# PROIECT_TSC_schematic.net
KiCad netlist of a schematic drawn in EAGLE
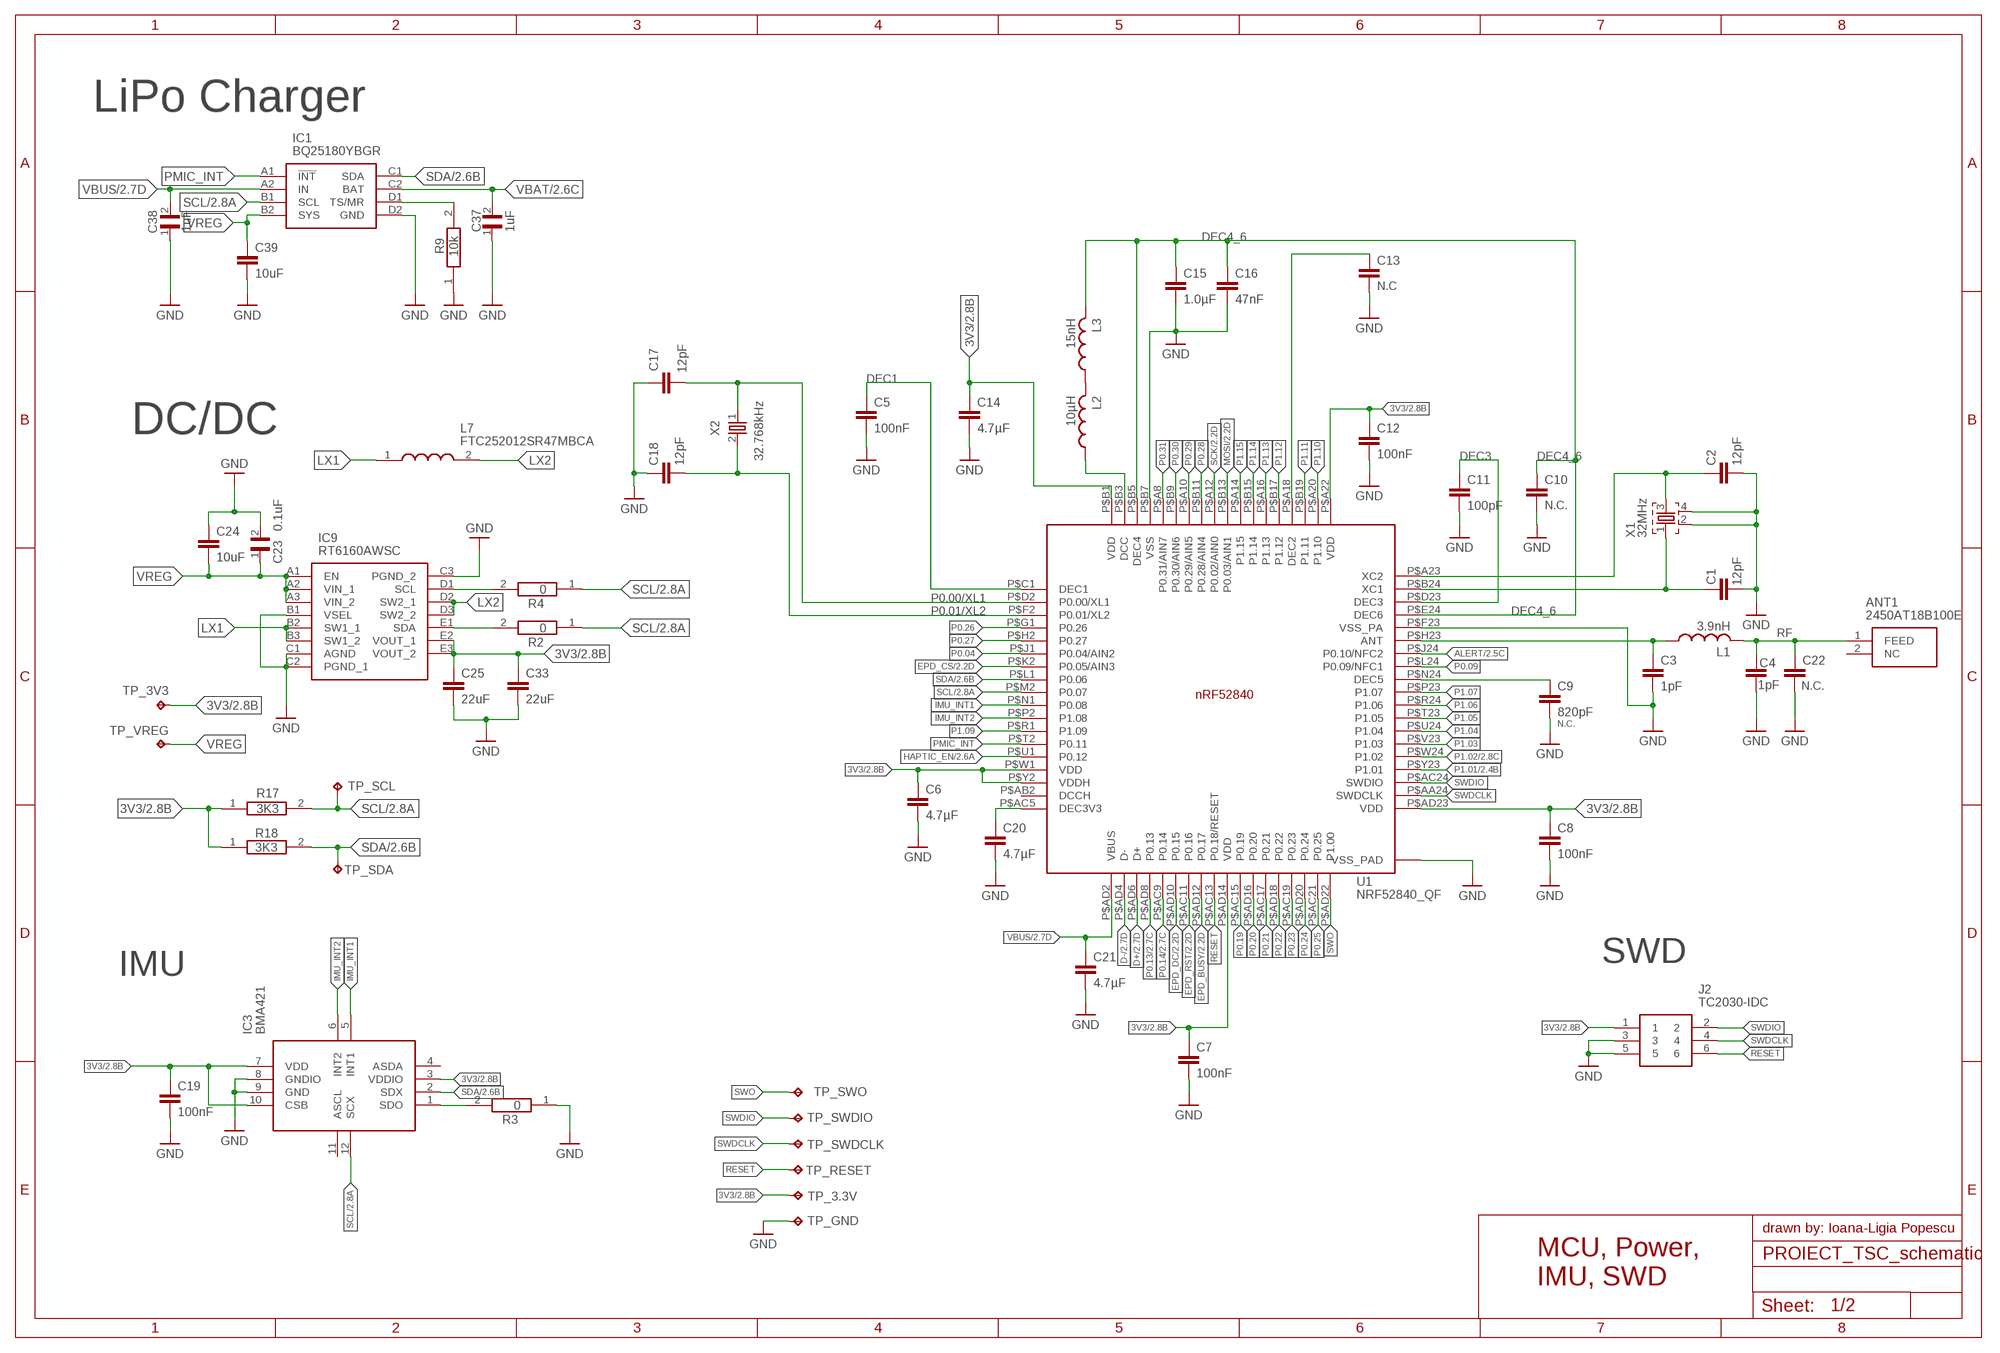
[diagram p0: schematic, sheet 1]
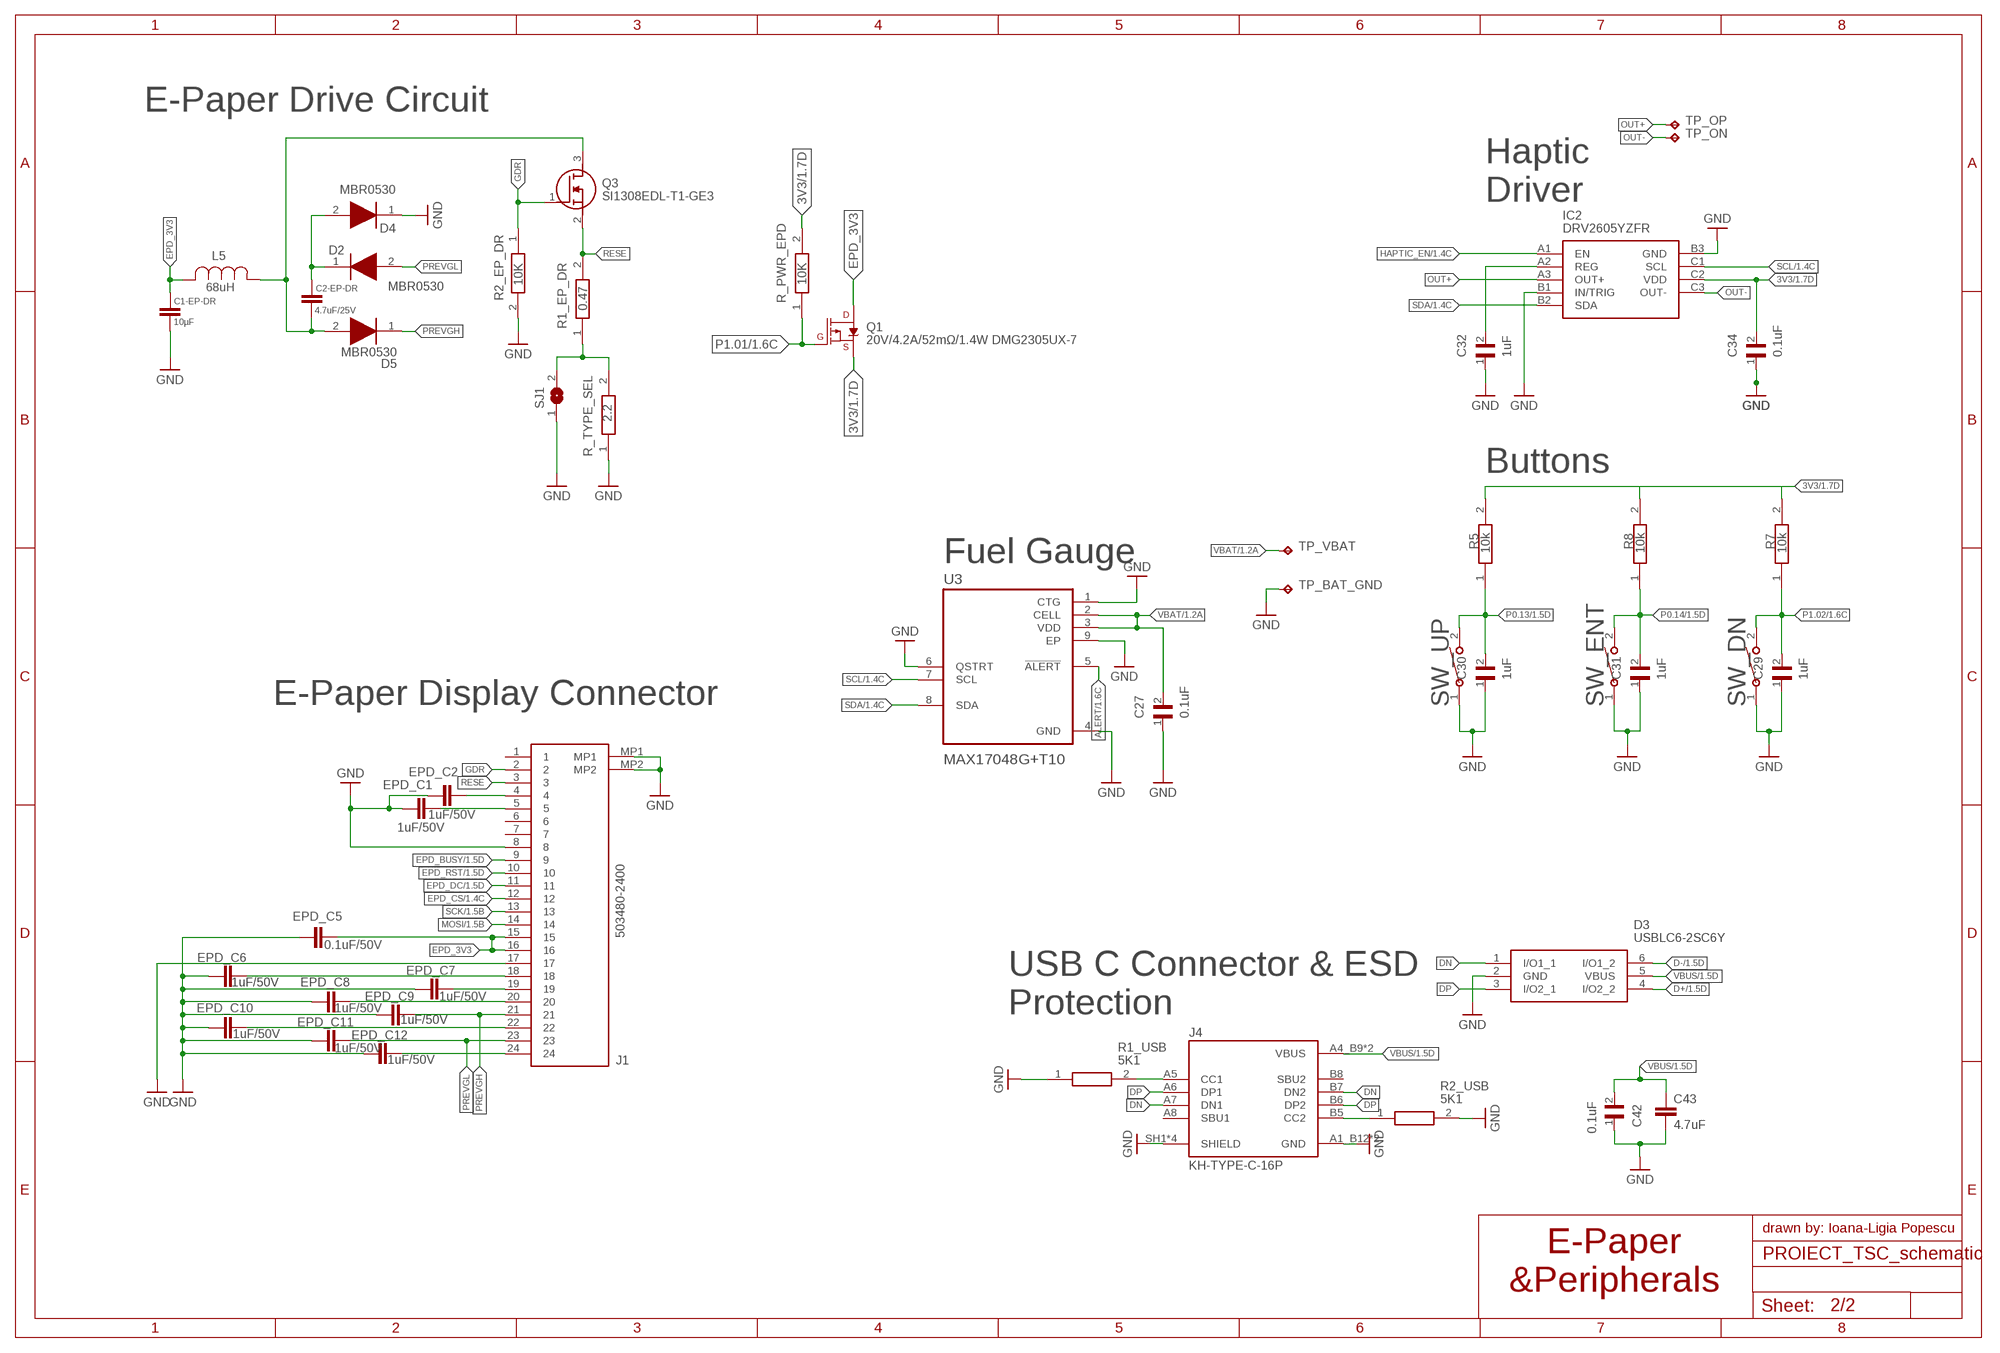
[diagram p1: schematic, sheet 2]

(export (version "E")
  (design (tool "Eeschema 10.0.6"))
  (components
    (comp (ref "ANT1")
      (value "2450AT18B100E")
      (footprint "eagle-import:2450AT18B100E_ANTC3216X140N")
      (fields (field (name "MOUSER_PART_NUMBER") "609-2450AT18B100E"))
      (libsource (lib "eagle-import") (part "2450AT18B100E_2450AT18B100E"))
    )
    (comp (ref "C1")
      (value "12pF")
      (footprint "eagle-import:NORDIC_NRF_3_RESC0201_L")
      (libsource (lib "eagle-import") (part "NORDIC_NRF_3_CAPACITOR_0201_L"))
    )
    (comp (ref "C2")
      (value "12pF")
      (footprint "eagle-import:NORDIC_NRF_3_RESC0201_L")
      (libsource (lib "eagle-import") (part "NORDIC_NRF_3_CAPACITOR_0201_L"))
    )
    (comp (ref "C3")
      (value "1pF")
      (footprint "eagle-import:NORDIC_NRF_3_RESC0201_L")
      (libsource (lib "eagle-import") (part "NORDIC_NRF_3_CAPACITOR_0201_L"))
    )
    (comp (ref "C4")
      (value "1pF")
      (footprint "eagle-import:NORDIC_NRF_3_RESC0201_L")
      (libsource (lib "eagle-import") (part "NORDIC_NRF_3_CAPACITOR_0201_L"))
    )
    (comp (ref "C5")
      (value "100nF")
      (footprint "eagle-import:NORDIC_NRF_3_RESC0201_L")
      (libsource (lib "eagle-import") (part "NORDIC_NRF_3_CAPACITOR_0201_L"))
    )
    (comp (ref "C6")
      (value "4.7µF")
      (footprint "eagle-import:ESP32_C6_LIBRARY_1_ESP32_WROVER_EAGLE-LTSPICE_C0402")
      (libsource (lib "eagle-import") (part "ESP32_C6_LIBRARY_1_ESP32_WROVER_EAGLE-LTSPICE_CC0402"))
    )
    (comp (ref "C7")
      (value "100nF")
      (footprint "eagle-import:NORDIC_NRF_3_RESC0201_L")
      (libsource (lib "eagle-import") (part "NORDIC_NRF_3_CAPACITOR_0201_L"))
    )
    (comp (ref "C8")
      (value "100nF")
      (footprint "eagle-import:NORDIC_NRF_3_RESC0201_L")
      (libsource (lib "eagle-import") (part "NORDIC_NRF_3_CAPACITOR_0201_L"))
    )
    (comp (ref "C9")
      (value "820pF")
      (footprint "eagle-import:NORDIC_NRF_3_RESC0201_L")
      (libsource (lib "eagle-import") (part "NORDIC_NRF_3_CAPACITOR_0201_L"))
    )
    (comp (ref "C10")
      (value "NORDIC_NRF_3_CAPACITOR_0201_L")
      (footprint "eagle-import:NORDIC_NRF_3_RESC0201_L")
      (libsource (lib "eagle-import") (part "NORDIC_NRF_3_CAPACITOR_0201_L"))
    )
    (comp (ref "C11")
      (value "100pF")
      (footprint "eagle-import:NORDIC_NRF_3_RESC0201_L")
      (libsource (lib "eagle-import") (part "NORDIC_NRF_3_CAPACITOR_0201_L"))
    )
    (comp (ref "C12")
      (value "100nF")
      (footprint "eagle-import:NORDIC_NRF_3_RESC0201_L")
      (libsource (lib "eagle-import") (part "NORDIC_NRF_3_CAPACITOR_0201_L"))
    )
    (comp (ref "C13")
      (value "NORDIC_NRF_3_CAPACITOR_0201_L")
      (footprint "eagle-import:NORDIC_NRF_3_RESC0201_L")
      (libsource (lib "eagle-import") (part "NORDIC_NRF_3_CAPACITOR_0201_L"))
    )
    (comp (ref "C14")
      (value "4.7µF")
      (footprint "eagle-import:ESP32_C6_LIBRARY_1_ESP32_WROVER_EAGLE-LTSPICE_C0402")
      (libsource (lib "eagle-import") (part "ESP32_C6_LIBRARY_1_ESP32_WROVER_EAGLE-LTSPICE_CC0402"))
    )
    (comp (ref "C15")
      (value "1.0µF")
      (footprint "eagle-import:ESP32_C6_LIBRARY_1_ESP32_WROVER_EAGLE-LTSPICE_C0402")
      (libsource (lib "eagle-import") (part "ESP32_C6_LIBRARY_1_ESP32_WROVER_EAGLE-LTSPICE_CC0402"))
    )
    (comp (ref "C16")
      (value "47nF")
      (footprint "eagle-import:NORDIC_NRF_3_RESC0201_L")
      (libsource (lib "eagle-import") (part "NORDIC_NRF_3_CAPACITOR_0201_L"))
    )
    (comp (ref "C17")
      (value "12pF")
      (footprint "eagle-import:NORDIC_NRF_3_RESC0201_L")
      (libsource (lib "eagle-import") (part "NORDIC_NRF_3_CAPACITOR_0201_L"))
    )
    (comp (ref "C18")
      (value "12pF")
      (footprint "eagle-import:NORDIC_NRF_3_RESC0201_L")
      (libsource (lib "eagle-import") (part "NORDIC_NRF_3_CAPACITOR_0201_L"))
    )
    (comp (ref "C19")
      (value "100nF")
      (footprint "eagle-import:NORDIC_NRF_3_RESC0201_L")
      (libsource (lib "eagle-import") (part "NORDIC_NRF_3_CAPACITOR_0201_L"))
    )
    (comp (ref "C20")
      (value "4.7µF")
      (footprint "eagle-import:ESP32_C6_LIBRARY_1_ESP32_WROVER_EAGLE-LTSPICE_C0402")
      (libsource (lib "eagle-import") (part "ESP32_C6_LIBRARY_1_ESP32_WROVER_EAGLE-LTSPICE_CC0402"))
    )
    (comp (ref "C21")
      (value "4.7µF")
      (footprint "eagle-import:ESP32_C6_LIBRARY_1_ESP32_WROVER_EAGLE-LTSPICE_C0402")
      (libsource (lib "eagle-import") (part "ESP32_C6_LIBRARY_1_ESP32_WROVER_EAGLE-LTSPICE_CC0402"))
    )
    (comp (ref "C22")
      (value "NORDIC_NRF_3_CAPACITOR_0201_L")
      (footprint "eagle-import:NORDIC_NRF_3_RESC0201_L")
      (libsource (lib "eagle-import") (part "NORDIC_NRF_3_CAPACITOR_0201_L"))
    )
    (comp (ref "C23")
      (value "0.1uF")
      (footprint "eagle-import:GRM011R60J152KE01L_2_CAPC0201X13N")
      (fields (field (name "MF") "Murata") (field (name "MP") "GRM011R60J152KE01L"))
      (libsource (lib "eagle-import") (part "GRM011R60J152KE01L_2_GRM011R60J152KE01L"))
    )
    (comp (ref "C24")
      (value "10uF")
      (footprint "eagle-import:ESP32_C6_LIBRARY_1_ESP32_WROVER_EAGLE-LTSPICE_C0402")
      (libsource (lib "eagle-import") (part "ESP32_C6_LIBRARY_1_ESP32_WROVER_EAGLE-LTSPICE_CC0402"))
    )
    (comp (ref "C25")
      (value "22uF")
      (footprint "eagle-import:ESP32_C6_LIBRARY_1_ESP32_WROVER_EAGLE-LTSPICE_C0402")
      (libsource (lib "eagle-import") (part "ESP32_C6_LIBRARY_1_ESP32_WROVER_EAGLE-LTSPICE_CC0402"))
    )
    (comp (ref "C33")
      (value "22uF")
      (footprint "eagle-import:ESP32_C6_LIBRARY_1_ESP32_WROVER_EAGLE-LTSPICE_C0402")
      (libsource (lib "eagle-import") (part "ESP32_C6_LIBRARY_1_ESP32_WROVER_EAGLE-LTSPICE_CC0402"))
    )
    (comp (ref "C37")
      (value "1uF")
      (footprint "eagle-import:GRM011R60J152KE01L_2_CAPC0201X13N")
      (fields (field (name "MF") "Murata") (field (name "MP") "GRM011R60J152KE01L"))
      (libsource (lib "eagle-import") (part "GRM011R60J152KE01L_2_GRM011R60J152KE01L"))
    )
    (comp (ref "C38")
      (value "1uF")
      (footprint "eagle-import:GRM011R60J152KE01L_2_CAPC0201X13N")
      (fields (field (name "MF") "Murata") (field (name "MP") "GRM011R60J152KE01L"))
      (libsource (lib "eagle-import") (part "GRM011R60J152KE01L_2_GRM011R60J152KE01L"))
    )
    (comp (ref "C39")
      (value "10uF")
      (footprint "eagle-import:ESP32_C6_LIBRARY_1_ESP32_WROVER_EAGLE-LTSPICE_C0402")
      (libsource (lib "eagle-import") (part "ESP32_C6_LIBRARY_1_ESP32_WROVER_EAGLE-LTSPICE_CC0402"))
    )
    (comp (ref "IC1")
      (value "BQ25180YBGR")
      (footprint "eagle-import:BQ25180YBGR_BGA8C40P2X4_100X155X50")
      (fields (field (name "MOUSER_PART_NUMBER") "595-BQ25180YBGR"))
      (libsource (lib "eagle-import") (part "BQ25180YBGR_BQ25180YBGR"))
    )
    (comp (ref "IC3")
      (value "BMA421")
      (footprint "eagle-import:BMA423_BMA423")
      (fields (field (name "ARROW_PART_NUMBER") "BMA423") (field (name "MOUSER_PART_NUMBER") "262-BMA423"))
      (libsource (lib "eagle-import") (part "BMA423_BMA423"))
    )
    (comp (ref "IC9")
      (value "RT6160AWSC")
      (footprint "eagle-import:RT6160AWSC_BGA15C40P3X5_140X230X60")
      (fields (field (name "MOUSER_PART_NUMBER") "835-RT6160AWSC"))
      (libsource (lib "eagle-import") (part "RT6160AWSC_RT6160AWSC"))
    )
    (comp (ref "J2")
      (value "TC2030-IDC")
      (footprint "eagle-import:TC2030-IDC_TC2030IDC")
      (libsource (lib "eagle-import") (part "TC2030-IDC_TC2030-IDC"))
    )
    (comp (ref "L1")
      (value "3.9nH")
      (footprint "eagle-import:NORDIC_NRF_2_RESC0402_L")
      (libsource (lib "eagle-import") (part "NORDIC_NRF_2_INDUCTOR_0402_L"))
    )
    (comp (ref "L2")
      (value "10µH")
      (footprint "eagle-import:NORDIC_NRF_2_RESC0402_L")
      (libsource (lib "eagle-import") (part "NORDIC_NRF_2_INDUCTOR_0402_L"))
    )
    (comp (ref "L3")
      (value "15nH")
      (footprint "eagle-import:NORDIC_NRF_2_RESC0402_L")
      (libsource (lib "eagle-import") (part "NORDIC_NRF_2_INDUCTOR_0402_L"))
    )
    (comp (ref "L7")
      (value "FTC252012SR47MBCA")
      (footprint "eagle-import:MLP2016SR47MT0S1_INDC2016X100N")
      (libsource (lib "eagle-import") (part "MLP2016SR47MT0S1_FTC252012SR47MBCA"))
    )
    (comp (ref "R2")
      (value "0")
      (footprint "eagle-import:CPF0201D7K68C1_0201")
      (libsource (lib "eagle-import") (part "CPF0201D7K68C1_CPF0201D7K68C1"))
    )
    (comp (ref "R3")
      (value "0")
      (footprint "eagle-import:CPF0201D7K68C1_0201")
      (libsource (lib "eagle-import") (part "CPF0201D7K68C1_CPF0201D7K68C1"))
    )
    (comp (ref "R4")
      (value "0")
      (footprint "eagle-import:CPF0201D7K68C1_0201")
      (libsource (lib "eagle-import") (part "CPF0201D7K68C1_CPF0201D7K68C1"))
    )
    (comp (ref "R9")
      (value "10k")
      (footprint "eagle-import:CPF0201D7K68C1_0201")
      (libsource (lib "eagle-import") (part "CPF0201D7K68C1_CPF0201D7K68C1"))
    )
    (comp (ref "R17")
      (value "3K3")
      (footprint "eagle-import:CPF0201D7K68C1_0201")
      (libsource (lib "eagle-import") (part "CPF0201D7K68C1_CPF0201D7K68C1"))
    )
    (comp (ref "R18")
      (value "3K3")
      (footprint "eagle-import:CPF0201D7K68C1_0201")
      (libsource (lib "eagle-import") (part "CPF0201D7K68C1_CPF0201D7K68C1"))
    )
    (comp (ref "TP_3.3V")
      (value "HECTOR_WATCH_1_TPTP20R")
      (footprint "eagle-import:HECTOR_WATCH_1_TP20R")
      (libsource (lib "eagle-import") (part "HECTOR_WATCH_1_TPTP20R"))
    )
    (comp (ref "TP_3V3")
      (value "HECTOR_WATCH_1_TPTP20R")
      (footprint "eagle-import:HECTOR_WATCH_1_TP20R")
      (libsource (lib "eagle-import") (part "HECTOR_WATCH_1_TPTP20R"))
    )
    (comp (ref "TP_GND")
      (value "HECTOR_WATCH_1_TPTP20R")
      (footprint "eagle-import:HECTOR_WATCH_1_TP20R")
      (libsource (lib "eagle-import") (part "HECTOR_WATCH_1_TPTP20R"))
    )
    (comp (ref "TP_RESET")
      (value "HECTOR_WATCH_1_TPTP20R")
      (footprint "eagle-import:HECTOR_WATCH_1_TP20R")
      (libsource (lib "eagle-import") (part "HECTOR_WATCH_1_TPTP20R"))
    )
    (comp (ref "TP_SCL")
      (value "HECTOR_WATCH_1_TPTP20R")
      (footprint "eagle-import:HECTOR_WATCH_1_TP20R")
      (libsource (lib "eagle-import") (part "HECTOR_WATCH_1_TPTP20R"))
    )
    (comp (ref "TP_SDA")
      (value "HECTOR_WATCH_1_TPTP20R")
      (footprint "eagle-import:HECTOR_WATCH_1_TP20R")
      (libsource (lib "eagle-import") (part "HECTOR_WATCH_1_TPTP20R"))
    )
    (comp (ref "TP_SWDCLK")
      (value "HECTOR_WATCH_1_TPTP20R")
      (footprint "eagle-import:HECTOR_WATCH_1_TP20R")
      (libsource (lib "eagle-import") (part "HECTOR_WATCH_1_TPTP20R"))
    )
    (comp (ref "TP_SWDIO")
      (value "HECTOR_WATCH_1_TPTP20R")
      (footprint "eagle-import:HECTOR_WATCH_1_TP20R")
      (libsource (lib "eagle-import") (part "HECTOR_WATCH_1_TPTP20R"))
    )
    (comp (ref "TP_SWO")
      (value "HECTOR_WATCH_1_TPTP20R")
      (footprint "eagle-import:HECTOR_WATCH_1_TP20R")
      (libsource (lib "eagle-import") (part "HECTOR_WATCH_1_TPTP20R"))
    )
    (comp (ref "TP_VREG")
      (value "HECTOR_WATCH_1_TPTP20R")
      (footprint "eagle-import:HECTOR_WATCH_1_TP20R")
      (libsource (lib "eagle-import") (part "HECTOR_WATCH_1_TPTP20R"))
    )
    (comp (ref "U1")
      (value "NRF52840_QF")
      (footprint "eagle-import:NORDIC_NRF_4_AQFN50P700X700X85_HS-74N")
      (libsource (lib "eagle-import") (part "NORDIC_NRF_4_NRF52840_QF"))
    )
    (comp (ref "X1")
      (value "32MHz")
      (footprint "eagle-import:NORDIC_NRF_BT-XTAL_2016_N")
      (libsource (lib "eagle-import") (part "NORDIC_NRF_XTAL_32MHZ"))
    )
    (comp (ref "X2")
      (value "32.768kHz")
      (footprint "eagle-import:NORDIC_NRF_1_XTAL_3215_N")
      (libsource (lib "eagle-import") (part "NORDIC_NRF_1_XTAL_32KHZ"))
    )
    (comp (ref "C1-EP-DR")
      (value "10µF")
      (footprint "eagle-import:ESP32_C6_LIBRARY_1_ESP32_WROVER_EAGLE-LTSPICE_C0402")
      (libsource (lib "eagle-import") (part "ESP32_C6_LIBRARY_1_ESP32_WROVER_EAGLE-LTSPICE_CC0402"))
    )
    (comp (ref "C2-EP-DR")
      (value "4.7uF/25V")
      (footprint "eagle-import:ESP32_C6_LIBRARY_1_ESP32_WROVER_EAGLE-LTSPICE_C0402")
      (libsource (lib "eagle-import") (part "ESP32_C6_LIBRARY_1_ESP32_WROVER_EAGLE-LTSPICE_CC0402"))
    )
    (comp (ref "C27")
      (value "0.1uF")
      (footprint "eagle-import:GRM011R60J152KE01L_2_CAPC0201X13N")
      (fields (field (name "MF") "Murata") (field (name "MP") "GRM011R60J152KE01L"))
      (libsource (lib "eagle-import") (part "GRM011R60J152KE01L_2_GRM011R60J152KE01L"))
    )
    (comp (ref "C29")
      (value "1uF")
      (footprint "eagle-import:GRM011R60J152KE01L_2_CAPC0201X13N")
      (fields (field (name "MF") "Murata") (field (name "MP") "GRM011R60J152KE01L"))
      (libsource (lib "eagle-import") (part "GRM011R60J152KE01L_2_GRM011R60J152KE01L"))
    )
    (comp (ref "C30")
      (value "1uF")
      (footprint "eagle-import:GRM011R60J152KE01L_2_CAPC0201X13N")
      (fields (field (name "MF") "Murata") (field (name "MP") "GRM011R60J152KE01L"))
      (libsource (lib "eagle-import") (part "GRM011R60J152KE01L_2_GRM011R60J152KE01L"))
    )
    (comp (ref "C31")
      (value "1uF")
      (footprint "eagle-import:GRM011R60J152KE01L_2_CAPC0201X13N")
      (fields (field (name "MF") "Murata") (field (name "MP") "GRM011R60J152KE01L"))
      (libsource (lib "eagle-import") (part "GRM011R60J152KE01L_2_GRM011R60J152KE01L"))
    )
    (comp (ref "C32")
      (value "1uF")
      (footprint "eagle-import:GRM011R60J152KE01L_2_CAPC0201X13N")
      (fields (field (name "MF") "Murata") (field (name "MP") "GRM011R60J152KE01L"))
      (libsource (lib "eagle-import") (part "GRM011R60J152KE01L_2_GRM011R60J152KE01L"))
    )
    (comp (ref "C34")
      (value "0.1uF")
      (footprint "eagle-import:GRM011R60J152KE01L_2_CAPC0201X13N")
      (fields (field (name "MF") "Murata") (field (name "MP") "GRM011R60J152KE01L"))
      (libsource (lib "eagle-import") (part "GRM011R60J152KE01L_2_GRM011R60J152KE01L"))
    )
    (comp (ref "C42")
      (value "0.1uF")
      (footprint "eagle-import:GRM011R60J152KE01L_2_CAPC0201X13N")
      (fields (field (name "MF") "Murata") (field (name "MP") "GRM011R60J152KE01L"))
      (libsource (lib "eagle-import") (part "GRM011R60J152KE01L_2_GRM011R60J152KE01L"))
    )
    (comp (ref "C43")
      (value "4.7uF")
      (footprint "eagle-import:ESP32_C6_LIBRARY_1_ESP32_WROVER_EAGLE-LTSPICE_C0402")
      (libsource (lib "eagle-import") (part "ESP32_C6_LIBRARY_1_ESP32_WROVER_EAGLE-LTSPICE_CC0402"))
    )
    (comp (ref "D2")
      (value "MBR0530")
      (footprint "eagle-import:ESP32_C6_LIBRARY_5_SOD3716X135N")
      (fields (field (name "MF") "ON Semiconductor"))
      (libsource (lib "eagle-import") (part "ESP32_C6_LIBRARY_5_MBR0530"))
    )
    (comp (ref "D3")
      (value "USBLC6-2SC6Y")
      (footprint "eagle-import:ESP32_C6_LIBRARY_3_SOT95P280X145-6N")
      (fields (field (name "MF") "STMicroelectronics"))
      (libsource (lib "eagle-import") (part "ESP32_C6_LIBRARY_3_USBLC6-2SC6Y"))
    )
    (comp (ref "D4")
      (value "MBR0530")
      (footprint "eagle-import:ESP32_C6_LIBRARY_5_SOD3716X135N")
      (fields (field (name "MF") "ON Semiconductor"))
      (libsource (lib "eagle-import") (part "ESP32_C6_LIBRARY_5_MBR0530"))
    )
    (comp (ref "D5")
      (value "MBR0530")
      (footprint "eagle-import:ESP32_C6_LIBRARY_5_SOD3716X135N")
      (fields (field (name "MF") "ON Semiconductor"))
      (libsource (lib "eagle-import") (part "ESP32_C6_LIBRARY_5_MBR0530"))
    )
    (comp (ref "EPD_C1")
      (value "1uF/50V")
      (footprint "eagle-import:ESP32_C6_LIBRARY_1_ESP32_WROVER_EAGLE-LTSPICE_C0402")
      (libsource (lib "eagle-import") (part "ESP32_C6_LIBRARY_1_ESP32_WROVER_EAGLE-LTSPICE_CC0402"))
    )
    (comp (ref "EPD_C2")
      (value "1uF/50V")
      (footprint "eagle-import:ESP32_C6_LIBRARY_1_ESP32_WROVER_EAGLE-LTSPICE_C0402")
      (libsource (lib "eagle-import") (part "ESP32_C6_LIBRARY_1_ESP32_WROVER_EAGLE-LTSPICE_CC0402"))
    )
    (comp (ref "EPD_C5")
      (value "0.1uF/50V")
      (footprint "eagle-import:ESP32_C6_LIBRARY_1_ESP32_WROVER_EAGLE-LTSPICE_C0402")
      (libsource (lib "eagle-import") (part "ESP32_C6_LIBRARY_1_ESP32_WROVER_EAGLE-LTSPICE_CC0402"))
    )
    (comp (ref "EPD_C6")
      (value "1uF/50V")
      (footprint "eagle-import:ESP32_C6_LIBRARY_1_ESP32_WROVER_EAGLE-LTSPICE_C0402")
      (libsource (lib "eagle-import") (part "ESP32_C6_LIBRARY_1_ESP32_WROVER_EAGLE-LTSPICE_CC0402"))
    )
    (comp (ref "EPD_C7")
      (value "1uF/50V")
      (footprint "eagle-import:ESP32_C6_LIBRARY_1_ESP32_WROVER_EAGLE-LTSPICE_C0402")
      (libsource (lib "eagle-import") (part "ESP32_C6_LIBRARY_1_ESP32_WROVER_EAGLE-LTSPICE_CC0402"))
    )
    (comp (ref "EPD_C8")
      (value "1uF/50V")
      (footprint "eagle-import:ESP32_C6_LIBRARY_1_ESP32_WROVER_EAGLE-LTSPICE_C0402")
      (libsource (lib "eagle-import") (part "ESP32_C6_LIBRARY_1_ESP32_WROVER_EAGLE-LTSPICE_CC0402"))
    )
    (comp (ref "EPD_C9")
      (value "1uF/50V")
      (footprint "eagle-import:ESP32_C6_LIBRARY_1_ESP32_WROVER_EAGLE-LTSPICE_C0402")
      (libsource (lib "eagle-import") (part "ESP32_C6_LIBRARY_1_ESP32_WROVER_EAGLE-LTSPICE_CC0402"))
    )
    (comp (ref "EPD_C10")
      (value "1uF/50V")
      (footprint "eagle-import:ESP32_C6_LIBRARY_1_ESP32_WROVER_EAGLE-LTSPICE_C0402")
      (libsource (lib "eagle-import") (part "ESP32_C6_LIBRARY_1_ESP32_WROVER_EAGLE-LTSPICE_CC0402"))
    )
    (comp (ref "EPD_C11")
      (value "1uF/50V")
      (footprint "eagle-import:ESP32_C6_LIBRARY_1_ESP32_WROVER_EAGLE-LTSPICE_C0402")
      (libsource (lib "eagle-import") (part "ESP32_C6_LIBRARY_1_ESP32_WROVER_EAGLE-LTSPICE_CC0402"))
    )
    (comp (ref "EPD_C12")
      (value "1uF/50V")
      (footprint "eagle-import:ESP32_C6_LIBRARY_1_ESP32_WROVER_EAGLE-LTSPICE_C0402")
      (libsource (lib "eagle-import") (part "ESP32_C6_LIBRARY_1_ESP32_WROVER_EAGLE-LTSPICE_CC0402"))
    )
    (comp (ref "IC2")
      (value "DRV2605YZFR")
      (footprint "eagle-import:DRV2605YZFR_BGA9C50P3X3_144X144X62")
      (libsource (lib "eagle-import") (part "DRV2605YZFR_DRV2605YZFR"))
    )
    (comp (ref "J1")
      (value "503480-2400")
      (footprint "eagle-import:503480-2400_5034802400")
      (fields (field (name "MOUSER_PART_NUMBER") "538-503480-2400"))
      (libsource (lib "eagle-import") (part "503480-2400_503480-2400"))
    )
    (comp (ref "J4")
      (value "KH-TYPE-C-16P")
      (footprint "eagle-import:KH-TYPE-C-16P_KINGHELM_KH-TYPE-C-16P")
      (fields (field (name "MF") "kinghelm"))
      (libsource (lib "eagle-import") (part "KH-TYPE-C-16P_KH-TYPE-C-16P"))
    )
    (comp (ref "L5")
      (value "68uH")
      (footprint "eagle-import:ESP32_C6_LIBRARY_2_IND_4828-WE-TPC_WRE")
      (fields
        (field (name "MANUFACTURER_PART_NUMBER") "744043680")
        (field (name "COPYRIGHT") "Copyright (C) 2024 Ultra Librarian. All rights reserved.")
      )
      (libsource (lib "eagle-import") (part "ESP32_C6_LIBRARY_2_744043680IND_4828-WE-TPC_WRE"))
    )
    (comp (ref "Q1")
      (value "20V/4.2A/52mΩ/1.4W DMG2305UX-7")
      (footprint "eagle-import:ESP32_C6_LIBRARY_4_ESP32_C6_LIBRARY_4_ESP32_C6_LIBRARY_4_ESP32_C6_LIBRARY_4_ESP32_WROVER_SPARKFUN-DISCRETESEMI_SOT23-3")
      (libsource (lib "eagle-import") (part "ESP32_C6_LIBRARY_4_ESP32_WROVER_SPARKFUN-DISCRETESEMI_MOSFET_PCH-DMG2305UX-7"))
    )
    (comp (ref "Q3")
      (value "SI1308EDL-T1-GE3")
      (footprint "eagle-import:ESP32_C6_LIBRARY_6_SOT65P210X110-3N")
      (fields (field (name "MF") "Vishay Siliconix"))
      (libsource (lib "eagle-import") (part "ESP32_C6_LIBRARY_6_SI1308EDL-T1-GE3"))
    )
    (comp (ref "R1_EP_DR")
      (value "0.47")
      (footprint "eagle-import:CPF0201D7K68C1_0201")
      (libsource (lib "eagle-import") (part "CPF0201D7K68C1_CPF0201D7K68C1"))
    )
    (comp (ref "R1_USB")
      (value "5K1")
      (footprint "eagle-import:CPF0201D7K68C1_0201")
      (libsource (lib "eagle-import") (part "CPF0201D7K68C1_CPF0201D7K68C1"))
    )
    (comp (ref "R2_EP_DR")
      (value "10K")
      (footprint "eagle-import:CPF0201D7K68C1_0201")
      (libsource (lib "eagle-import") (part "CPF0201D7K68C1_CPF0201D7K68C1"))
    )
    (comp (ref "R2_USB")
      (value "5K1")
      (footprint "eagle-import:CPF0201D7K68C1_0201")
      (libsource (lib "eagle-import") (part "CPF0201D7K68C1_CPF0201D7K68C1"))
    )
    (comp (ref "R5")
      (value "10k")
      (footprint "eagle-import:CPF0201D7K68C1_0201")
      (libsource (lib "eagle-import") (part "CPF0201D7K68C1_CPF0201D7K68C1"))
    )
    (comp (ref "R7")
      (value "10k")
      (footprint "eagle-import:CPF0201D7K68C1_0201")
      (libsource (lib "eagle-import") (part "CPF0201D7K68C1_CPF0201D7K68C1"))
    )
    (comp (ref "R8")
      (value "10k")
      (footprint "eagle-import:CPF0201D7K68C1_0201")
      (libsource (lib "eagle-import") (part "CPF0201D7K68C1_CPF0201D7K68C1"))
    )
    (comp (ref "R_PWR_EPD")
      (value "10K")
      (footprint "eagle-import:CPF0201D7K68C1_0201")
      (libsource (lib "eagle-import") (part "CPF0201D7K68C1_CPF0201D7K68C1"))
    )
    (comp (ref "R_TYPE_SEL")
      (value "2.2")
      (footprint "eagle-import:CPF0201D7K68C1_0201")
      (libsource (lib "eagle-import") (part "CPF0201D7K68C1_CPF0201D7K68C1"))
    )
    (comp (ref "SJ1")
      (value "ESP32_C6_LIBRARY_7_JUMPER_SJ")
      (footprint "eagle-import:ESP32_C6_LIBRARY_7_JUMPER_SJ")
      (libsource (lib "eagle-import") (part "ESP32_C6_LIBRARY_7_JUMPER_SJ"))
    )
    (comp (ref "SW_DN")
      (value "2025-10-22_07-23-44_LIBRARY_EVP-AKE31ASW_EVP-AKE31A_PAN")
      (footprint "eagle-import:2025-10-22_07-23-44_LIBRARY_SW_EVP-AKE31A_PAN")
      (fields
        (field (name "MANUFACTURER_PART_NUMBER") "EVP-AKE31A")
        (field (name "COPYRIGHT") "Copyright (C) 2025 Ultra Librarian. All rights reserved.")
      )
      (libsource (lib "eagle-import") (part "2025-10-22_07-23-44_LIBRARY_EVP-AKE31ASW_EVP-AKE31A_PAN"))
    )
    (comp (ref "SW_ENT")
      (value "2025-10-22_07-23-44_LIBRARY_EVP-AKE31ASW_EVP-AKE31A_PAN")
      (footprint "eagle-import:2025-10-22_07-23-44_LIBRARY_SW_EVP-AKE31A_PAN")
      (fields
        (field (name "MANUFACTURER_PART_NUMBER") "EVP-AKE31A")
        (field (name "COPYRIGHT") "Copyright (C) 2025 Ultra Librarian. All rights reserved.")
      )
      (libsource (lib "eagle-import") (part "2025-10-22_07-23-44_LIBRARY_EVP-AKE31ASW_EVP-AKE31A_PAN"))
    )
    (comp (ref "SW_UP")
      (value "2025-10-22_07-23-44_LIBRARY_EVP-AKE31ASW_EVP-AKE31A_PAN")
      (footprint "eagle-import:2025-10-22_07-23-44_LIBRARY_SW_EVP-AKE31A_PAN")
      (fields
        (field (name "MANUFACTURER_PART_NUMBER") "EVP-AKE31A")
        (field (name "COPYRIGHT") "Copyright (C) 2025 Ultra Librarian. All rights reserved.")
      )
      (libsource (lib "eagle-import") (part "2025-10-22_07-23-44_LIBRARY_EVP-AKE31ASW_EVP-AKE31A_PAN"))
    )
    (comp (ref "TP_BAT_GND")
      (value "HECTOR_WATCH_1_TPTP20R")
      (footprint "eagle-import:HECTOR_WATCH_1_TP20R")
      (libsource (lib "eagle-import") (part "HECTOR_WATCH_1_TPTP20R"))
    )
    (comp (ref "TP_ON")
      (value "HECTOR_WATCH_1_TPTP20R")
      (footprint "eagle-import:HECTOR_WATCH_1_TP20R")
      (libsource (lib "eagle-import") (part "HECTOR_WATCH_1_TPTP20R"))
    )
    (comp (ref "TP_OP")
      (value "HECTOR_WATCH_1_TPTP20R")
      (footprint "eagle-import:HECTOR_WATCH_1_TP20R")
      (libsource (lib "eagle-import") (part "HECTOR_WATCH_1_TPTP20R"))
    )
    (comp (ref "TP_VBAT")
      (value "HECTOR_WATCH_1_TPTP20R")
      (footprint "eagle-import:HECTOR_WATCH_1_TP20R")
      (libsource (lib "eagle-import") (part "HECTOR_WATCH_1_TPTP20R"))
    )
    (comp (ref "U3")
      (value "MAX17048G+T10")
      (footprint "eagle-import:ESP32_C6_LIBRARY_SON50P200X200X80-9N")
      (fields (field (name "MF") "Analog Devices"))
      (libsource (lib "eagle-import") (part "ESP32_C6_LIBRARY_MAX17048G+T10"))
    )
  )
  (nets
    (net (code "1") (name "3V3") (class "Default")
      (node (ref "C12") (pin "1") (pinfunction "1_1") (pintype "passive"))
      (node (ref "C14") (pin "1") (pinfunction "1_1") (pintype "passive"))
      (node (ref "C19") (pin "1") (pinfunction "1_1") (pintype "passive"))
      (node (ref "C25") (pin "1") (pinfunction "1_1") (pintype "passive"))
      (node (ref "C33") (pin "1") (pinfunction "1_1") (pintype "passive"))
      (node (ref "C34") (pin "2") (pinfunction "2_2") (pintype "passive"))
      (node (ref "C6") (pin "1") (pinfunction "1_1") (pintype "passive"))
      (node (ref "C7") (pin "1") (pinfunction "1_1") (pintype "passive"))
      (node (ref "C8") (pin "1") (pinfunction "1_1") (pintype "passive"))
      (node (ref "IC2") (pin "C2") (pinfunction "VDD_C2") (pintype "bidirectional"))
      (node (ref "IC3") (pin "10") (pinfunction "CSB_10") (pintype "bidirectional"))
      (node (ref "IC3") (pin "3") (pinfunction "VDDIO_3") (pintype "bidirectional"))
      (node (ref "IC3") (pin "7") (pinfunction "VDD_7") (pintype "bidirectional"))
      (node (ref "IC9") (pin "E2") (pinfunction "VOUT_1_E2") (pintype "bidirectional"))
      (node (ref "IC9") (pin "E3") (pinfunction "VOUT_2_E3") (pintype "bidirectional"))
      (node (ref "J2") (pin "1") (pinfunction "1_1") (pintype "bidirectional"))
      (node (ref "Q1") (pin "2") (pinfunction "S_2") (pintype "bidirectional"))
      (node (ref "R17") (pin "1") (pinfunction "1_1") (pintype "bidirectional"))
      (node (ref "R18") (pin "1") (pinfunction "1_1") (pintype "bidirectional"))
      (node (ref "R5") (pin "2") (pinfunction "2_2") (pintype "bidirectional"))
      (node (ref "R_PWR_EPD") (pin "2") (pinfunction "2_2") (pintype "bidirectional"))
      (node (ref "TP_3.3V") (pin "TP") (pinfunction "TP_TP") (pintype "input"))
      (node (ref "TP_3V3") (pin "TP") (pinfunction "TP_TP") (pintype "input"))
      (node (ref "U1") (pin "P$A22") (pinfunction "VDD_P$A22") (pintype "power_in"))
      (node (ref "U1") (pin "P$AD14") (pinfunction "VDD_P$AD14") (pintype "power_in"))
      (node (ref "U1") (pin "P$AD23") (pinfunction "VDD_P$AD23") (pintype "power_in"))
      (node (ref "U1") (pin "P$B1") (pinfunction "VDD_P$B1") (pintype "power_in"))
      (node (ref "U1") (pin "P$W1") (pinfunction "VDD_P$W1") (pintype "power_in"))
      (node (ref "U1") (pin "P$Y2") (pinfunction "VDDH_P$Y2") (pintype "power_in"))
    )
    (net (code "2") (name "ALERT") (class "Default")
      (node (ref "U1") (pin "P$J24") (pinfunction "P0.10/NFC2_P$J24") (pintype "bidirectional"))
      (node (ref "U3") (pin "5") (pinfunction "~{ALERT}_5") (pintype "output"))
    )
    (net (code "3") (name "D+") (class "Default")
      (node (ref "D3") (pin "4") (pinfunction "I/O2_2_4") (pintype "bidirectional"))
      (node (ref "U1") (pin "P$AD6") (pinfunction "D+_P$AD6") (pintype "bidirectional"))
    )
    (net (code "4") (name "D-") (class "Default")
      (node (ref "D3") (pin "6") (pinfunction "I/O1_2_6") (pintype "bidirectional"))
      (node (ref "U1") (pin "P$AD4") (pinfunction "D-_P$AD4") (pintype "bidirectional"))
    )
    (net (code "5") (name "DN") (class "Default")
      (node (ref "D3") (pin "1") (pinfunction "I/O1_1_1") (pintype "bidirectional"))
      (node (ref "J4") (pin "A7") (pinfunction "DN1_A7") (pintype "bidirectional"))
      (node (ref "J4") (pin "B7") (pinfunction "DN2_B7") (pintype "bidirectional"))
    )
    (net (code "6") (name "DP") (class "Default")
      (node (ref "D3") (pin "3") (pinfunction "I/O2_1_3") (pintype "bidirectional"))
      (node (ref "J4") (pin "A6") (pinfunction "DP1_A6") (pintype "bidirectional"))
      (node (ref "J4") (pin "B6") (pinfunction "DP2_B6") (pintype "bidirectional"))
    )
    (net (code "7") (name "EPD_3V3") (class "Default")
      (node (ref "C1-EP-DR") (pin "1") (pinfunction "1_1") (pintype "passive"))
      (node (ref "EPD_C5") (pin "2") (pinfunction "2_2") (pintype "passive"))
      (node (ref "J1") (pin "15") (pinfunction "15_15") (pintype "bidirectional"))
      (node (ref "J1") (pin "16") (pinfunction "16_16") (pintype "bidirectional"))
      (node (ref "L5") (pin "2") (pinfunction "2_2") (pintype "passive"))
      (node (ref "Q1") (pin "3") (pinfunction "D_3") (pintype "bidirectional"))
    )
    (net (code "8") (name "EPD_BUSY") (class "Default")
      (node (ref "J1") (pin "9") (pinfunction "9_9") (pintype "bidirectional"))
      (node (ref "U1") (pin "P$AD12") (pinfunction "P0.17_P$AD12") (pintype "bidirectional"))
    )
    (net (code "9") (name "EPD_CS") (class "Default")
      (node (ref "J1") (pin "12") (pinfunction "12_12") (pintype "bidirectional"))
      (node (ref "U1") (pin "P$K2") (pinfunction "P0.05/AIN3_P$K2") (pintype "bidirectional"))
    )
    (net (code "10") (name "EPD_DC") (class "Default")
      (node (ref "J1") (pin "11") (pinfunction "11_11") (pintype "bidirectional"))
      (node (ref "U1") (pin "P$AD10") (pinfunction "P0.15_P$AD10") (pintype "bidirectional"))
    )
    (net (code "11") (name "EPD_RST") (class "Default")
      (node (ref "J1") (pin "10") (pinfunction "10_10") (pintype "bidirectional"))
      (node (ref "U1") (pin "P$AC11") (pinfunction "P0.16_P$AC11") (pintype "bidirectional"))
    )
    (net (code "12") (name "GDR") (class "Default")
      (node (ref "J1") (pin "2") (pinfunction "2_2") (pintype "bidirectional"))
      (node (ref "Q3") (pin "1") (pinfunction "G_1") (pintype "bidirectional"))
      (node (ref "R2_EP_DR") (pin "1") (pinfunction "1_1") (pintype "bidirectional"))
    )
    (net (code "13") (name "GND") (class "Default")
      (node (ref "C1") (pin "1") (pinfunction "1_1") (pintype "passive"))
      (node (ref "C1-EP-DR") (pin "2") (pinfunction "2_2") (pintype "passive"))
      (node (ref "C10") (pin "2") (pinfunction "2_2") (pintype "passive"))
      (node (ref "C11") (pin "2") (pinfunction "2_2") (pintype "passive"))
      (node (ref "C12") (pin "2") (pinfunction "2_2") (pintype "passive"))
      (node (ref "C13") (pin "2") (pinfunction "2_2") (pintype "passive"))
      (node (ref "C14") (pin "2") (pinfunction "2_2") (pintype "passive"))
      (node (ref "C15") (pin "2") (pinfunction "2_2") (pintype "passive"))
      (node (ref "C16") (pin "2") (pinfunction "2_2") (pintype "passive"))
      (node (ref "C17") (pin "2") (pinfunction "2_2") (pintype "passive"))
      (node (ref "C18") (pin "1") (pinfunction "1_1") (pintype "passive"))
      (node (ref "C19") (pin "2") (pinfunction "2_2") (pintype "passive"))
      (node (ref "C2") (pin "2") (pinfunction "2_2") (pintype "passive"))
      (node (ref "C20") (pin "2") (pinfunction "2_2") (pintype "passive"))
      (node (ref "C21") (pin "2") (pinfunction "2_2") (pintype "passive"))
      (node (ref "C22") (pin "2") (pinfunction "2_2") (pintype "passive"))
      (node (ref "C23") (pin "2") (pinfunction "2_2") (pintype "passive"))
      (node (ref "C24") (pin "1") (pinfunction "1_1") (pintype "passive"))
      (node (ref "C25") (pin "2") (pinfunction "2_2") (pintype "passive"))
      (node (ref "C27") (pin "1") (pinfunction "1_1") (pintype "passive"))
      (node (ref "C29") (pin "1") (pinfunction "1_1") (pintype "passive"))
      (node (ref "C3") (pin "2") (pinfunction "2_2") (pintype "passive"))
      (node (ref "C30") (pin "1") (pinfunction "1_1") (pintype "passive"))
      (node (ref "C31") (pin "1") (pinfunction "1_1") (pintype "passive"))
      (node (ref "C32") (pin "1") (pinfunction "1_1") (pintype "passive"))
      (node (ref "C33") (pin "2") (pinfunction "2_2") (pintype "passive"))
      (node (ref "C34") (pin "1") (pinfunction "1_1") (pintype "passive"))
      (node (ref "C37") (pin "1") (pinfunction "1_1") (pintype "passive"))
      (node (ref "C38") (pin "1") (pinfunction "1_1") (pintype "passive"))
      (node (ref "C39") (pin "2") (pinfunction "2_2") (pintype "passive"))
      (node (ref "C4") (pin "1") (pinfunction "1_1") (pintype "passive"))
      (node (ref "C42") (pin "1") (pinfunction "1_1") (pintype "passive"))
      (node (ref "C43") (pin "2") (pinfunction "2_2") (pintype "passive"))
      (node (ref "C5") (pin "2") (pinfunction "2_2") (pintype "passive"))
      (node (ref "C6") (pin "2") (pinfunction "2_2") (pintype "passive"))
      (node (ref "C7") (pin "2") (pinfunction "2_2") (pintype "passive"))
      (node (ref "C8") (pin "2") (pinfunction "2_2") (pintype "passive"))
      (node (ref "C9") (pin "2") (pinfunction "2_2") (pintype "passive"))
      (node (ref "D3") (pin "2") (pinfunction "GND_2") (pintype "bidirectional"))
      (node (ref "D4") (pin "1") (pinfunction "K_1") (pintype "bidirectional"))
      (node (ref "EPD_C1") (pin "1") (pinfunction "1_1") (pintype "passive"))
      (node (ref "EPD_C10") (pin "1") (pinfunction "1_1") (pintype "passive"))
      (node (ref "EPD_C11") (pin "1") (pinfunction "1_1") (pintype "passive"))
      (node (ref "EPD_C12") (pin "1") (pinfunction "1_1") (pintype "passive"))
      (node (ref "EPD_C2") (pin "1") (pinfunction "1_1") (pintype "passive"))
      (node (ref "EPD_C5") (pin "1") (pinfunction "1_1") (pintype "passive"))
      (node (ref "EPD_C6") (pin "1") (pinfunction "1_1") (pintype "passive"))
      (node (ref "EPD_C7") (pin "1") (pinfunction "1_1") (pintype "passive"))
      (node (ref "EPD_C8") (pin "1") (pinfunction "1_1") (pintype "passive"))
      (node (ref "EPD_C9") (pin "1") (pinfunction "1_1") (pintype "passive"))
      (node (ref "IC1") (pin "D2") (pinfunction "GND_D2") (pintype "bidirectional"))
      (node (ref "IC2") (pin "B1") (pinfunction "IN/TRIG_B1") (pintype "bidirectional"))
      (node (ref "IC2") (pin "B3") (pinfunction "GND_B3") (pintype "bidirectional"))
      (node (ref "IC3") (pin "8") (pinfunction "GNDIO_8") (pintype "bidirectional"))
      (node (ref "IC3") (pin "9") (pinfunction "GND_9") (pintype "bidirectional"))
      (node (ref "IC9") (pin "B1") (pinfunction "VSEL_B1") (pintype "bidirectional"))
      (node (ref "IC9") (pin "C1") (pinfunction "AGND_C1") (pintype "bidirectional"))
      (node (ref "IC9") (pin "C2") (pinfunction "PGND_1_C2") (pintype "bidirectional"))
      (node (ref "IC9") (pin "C3") (pinfunction "PGND_2_C3") (pintype "bidirectional"))
      (node (ref "J1") (pin "17") (pinfunction "17_17") (pintype "bidirectional"))
      (node (ref "J1") (pin "8") (pinfunction "8_8") (pintype "bidirectional"))
      (node (ref "J1") (pin "MP1") (pinfunction "MP1_MP1") (pintype "bidirectional"))
      (node (ref "J1") (pin "MP2") (pinfunction "MP2_MP2") (pintype "bidirectional"))
      (node (ref "J2") (pin "3") (pinfunction "3_3") (pintype "bidirectional"))
      (node (ref "J2") (pin "5") (pinfunction "5_5") (pintype "bidirectional"))
      (node (ref "J4") (pin "A12_B1") (pinfunction "GND_A12_B1") (pintype "power_in"))
      (node (ref "J4") (pin "A1_B12") (pinfunction "GND_A1_B12") (pintype "power_in"))
      (node (ref "J4") (pin "SH1") (pinfunction "SHIELD_SH1") (pintype "passive"))
      (node (ref "J4") (pin "SH2") (pinfunction "SHIELD_SH2") (pintype "passive"))
      (node (ref "J4") (pin "SH3") (pinfunction "SHIELD_SH3") (pintype "passive"))
      (node (ref "J4") (pin "SH4") (pinfunction "SHIELD_SH4") (pintype "passive"))
      (node (ref "R1_USB") (pin "1") (pinfunction "1_1") (pintype "bidirectional"))
      (node (ref "R2_EP_DR") (pin "2") (pinfunction "2_2") (pintype "bidirectional"))
      (node (ref "R2_USB") (pin "2") (pinfunction "2_2") (pintype "bidirectional"))
      (node (ref "R3") (pin "1") (pinfunction "1_1") (pintype "bidirectional"))
      (node (ref "R9") (pin "1") (pinfunction "1_1") (pintype "bidirectional"))
      (node (ref "R_TYPE_SEL") (pin "1") (pinfunction "1_1") (pintype "bidirectional"))
      (node (ref "SJ1") (pin "1") (pinfunction "1_1") (pintype "passive"))
      (node (ref "SW_DN") (pin "1") (pinfunction "1_1") (pintype "passive"))
      (node (ref "SW_ENT") (pin "1") (pinfunction "1_1") (pintype "passive"))
      (node (ref "SW_UP") (pin "1") (pinfunction "1_1") (pintype "passive"))
      (node (ref "TP_BAT_GND") (pin "TP") (pinfunction "TP_TP") (pintype "input"))
      (node (ref "TP_GND") (pin "TP") (pinfunction "TP_TP") (pintype "input"))
      (node (ref "U1") (pin "P$74") (pinfunction "VSS_PAD_P$74") (pintype "bidirectional"))
      (node (ref "U1") (pin "P$75") (pinfunction "VSS_PAD_P$75") (pintype "bidirectional"))
      (node (ref "U1") (pin "P$76") (pinfunction "VSS_PAD_P$76") (pintype "bidirectional"))
      (node (ref "U1") (pin "P$77") (pinfunction "VSS_PAD_P$77") (pintype "bidirectional"))
      (node (ref "U1") (pin "P$78") (pinfunction "VSS_PAD_P$78") (pintype "bidirectional"))
      (node (ref "U1") (pin "P$79") (pinfunction "VSS_PAD_P$79") (pintype "bidirectional"))
      (node (ref "U1") (pin "P$80") (pinfunction "VSS_PAD_P$80") (pintype "bidirectional"))
      (node (ref "U1") (pin "P$81") (pinfunction "VSS_PAD_P$81") (pintype "bidirectional"))
      (node (ref "U1") (pin "P$82") (pinfunction "VSS_PAD_P$82") (pintype "bidirectional"))
      (node (ref "U1") (pin "P$83") (pinfunction "VSS_PAD_P$83") (pintype "bidirectional"))
      (node (ref "U1") (pin "P$84") (pinfunction "VSS_PAD_P$84") (pintype "bidirectional"))
      (node (ref "U1") (pin "P$85") (pinfunction "VSS_PAD_P$85") (pintype "bidirectional"))
      (node (ref "U1") (pin "P$86") (pinfunction "VSS_PAD_P$86") (pintype "bidirectional"))
      (node (ref "U1") (pin "P$87") (pinfunction "VSS_PAD_P$87") (pintype "bidirectional"))
      (node (ref "U1") (pin "P$88") (pinfunction "VSS_PAD_P$88") (pintype "bidirectional"))
      (node (ref "U1") (pin "P$89") (pinfunction "VSS_PAD_P$89") (pintype "bidirectional"))
      (node (ref "U1") (pin "P$90") (pinfunction "VSS_PAD_P$90") (pintype "bidirectional"))
      (node (ref "U1") (pin "P$B7") (pinfunction "VSS_P$B7") (pintype "power_in"))
      (node (ref "U1") (pin "P$F23") (pinfunction "VSS_PA_P$F23") (pintype "bidirectional"))
      (node (ref "U3") (pin "1") (pinfunction "CTG_1") (pintype "power_in"))
      (node (ref "U3") (pin "4") (pinfunction "GND_4") (pintype "power_in"))
      (node (ref "U3") (pin "6") (pinfunction "QSTRT_6") (pintype "input"))
      (node (ref "U3") (pin "9") (pinfunction "EP_9") (pintype "power_in"))
      (node (ref "X1") (pin "2") (pinfunction "2_2") (pintype "passive"))
      (node (ref "X1") (pin "4") (pinfunction "4_4") (pintype "passive"))
    )
    (net (code "14") (name "HAPTIC_EN") (class "Default")
      (node (ref "IC2") (pin "A1") (pinfunction "EN_A1") (pintype "bidirectional"))
      (node (ref "U1") (pin "P$U1") (pinfunction "P0.12_P$U1") (pintype "bidirectional"))
    )
    (net (code "15") (name "IMU_INT1") (class "Default")
      (node (ref "IC3") (pin "5") (pinfunction "INT1_5") (pintype "bidirectional"))
      (node (ref "U1") (pin "P$N1") (pinfunction "P0.08_P$N1") (pintype "bidirectional"))
    )
    (net (code "16") (name "IMU_INT2") (class "Default")
      (node (ref "IC3") (pin "6") (pinfunction "INT2_6") (pintype "bidirectional"))
      (node (ref "U1") (pin "P$P2") (pinfunction "P1.08_P$P2") (pintype "bidirectional"))
    )
    (net (code "17") (name "LX1") (class "Default")
      (node (ref "IC9") (pin "B2") (pinfunction "SW1_1_B2") (pintype "bidirectional"))
      (node (ref "IC9") (pin "B3") (pinfunction "SW1_2_B3") (pintype "bidirectional"))
      (node (ref "L7") (pin "1") (pinfunction "1_1") (pintype "bidirectional"))
    )
    (net (code "18") (name "LX2") (class "Default")
      (node (ref "IC9") (pin "D2") (pinfunction "SW2_1_D2") (pintype "bidirectional"))
      (node (ref "IC9") (pin "D3") (pinfunction "SW2_2_D3") (pintype "bidirectional"))
      (node (ref "L7") (pin "2") (pinfunction "2_2") (pintype "bidirectional"))
    )
    (net (code "19") (name "MOSI") (class "Default")
      (node (ref "J1") (pin "14") (pinfunction "14_14") (pintype "bidirectional"))
      (node (ref "U1") (pin "P$B13") (pinfunction "P0.03/AIN1_P$B13") (pintype "bidirectional"))
    )
    (net (code "20") (name "Net-(ANT1-FEED)") (class "Default")
      (node (ref "ANT1") (pin "1") (pinfunction "FEED_1") (pintype "input"))
      (node (ref "C22") (pin "1") (pinfunction "1_1") (pintype "passive"))
      (node (ref "C4") (pin "2") (pinfunction "2_2") (pintype "passive"))
      (node (ref "L1") (pin "2") (pinfunction "2_2") (pintype "passive"))
    )
    (net (code "21") (name "Net-(D2-K)") (class "Default")
      (node (ref "C2-EP-DR") (pin "1") (pinfunction "1_1") (pintype "passive"))
      (node (ref "D2") (pin "1") (pinfunction "K_1") (pintype "bidirectional"))
      (node (ref "D4") (pin "2") (pinfunction "A_2") (pintype "bidirectional"))
    )
    (net (code "22") (name "Net-(D5-A)") (class "Default")
      (node (ref "C2-EP-DR") (pin "2") (pinfunction "2_2") (pintype "passive"))
      (node (ref "D5") (pin "2") (pinfunction "A_2") (pintype "bidirectional"))
      (node (ref "L5") (pin "1") (pinfunction "1_1") (pintype "passive"))
      (node (ref "Q3") (pin "3") (pinfunction "D_3") (pintype "bidirectional"))
    )
    (net (code "23") (name "Net-(EPD_C1-Pad2)") (class "Default")
      (node (ref "EPD_C1") (pin "2") (pinfunction "2_2") (pintype "passive"))
      (node (ref "J1") (pin "5") (pinfunction "5_5") (pintype "bidirectional"))
    )
    (net (code "24") (name "Net-(EPD_C2-Pad2)") (class "Default")
      (node (ref "EPD_C2") (pin "2") (pinfunction "2_2") (pintype "passive"))
      (node (ref "J1") (pin "4") (pinfunction "4_4") (pintype "bidirectional"))
    )
    (net (code "25") (name "Net-(EPD_C6-Pad2)") (class "Default")
      (node (ref "EPD_C6") (pin "2") (pinfunction "2_2") (pintype "passive"))
      (node (ref "J1") (pin "18") (pinfunction "18_18") (pintype "bidirectional"))
    )
    (net (code "26") (name "Net-(EPD_C7-Pad2)") (class "Default")
      (node (ref "EPD_C7") (pin "2") (pinfunction "2_2") (pintype "passive"))
      (node (ref "J1") (pin "19") (pinfunction "19_19") (pintype "bidirectional"))
    )
    (net (code "27") (name "Net-(EPD_C8-Pad2)") (class "Default")
      (node (ref "EPD_C8") (pin "2") (pinfunction "2_2") (pintype "passive"))
      (node (ref "J1") (pin "20") (pinfunction "20_20") (pintype "bidirectional"))
    )
    (net (code "28") (name "Net-(EPD_C10-Pad2)") (class "Default")
      (node (ref "EPD_C10") (pin "2") (pinfunction "2_2") (pintype "passive"))
      (node (ref "J1") (pin "22") (pinfunction "22_22") (pintype "bidirectional"))
    )
    (net (code "29") (name "Net-(EPD_C12-Pad2)") (class "Default")
      (node (ref "EPD_C12") (pin "2") (pinfunction "2_2") (pintype "passive"))
      (node (ref "J1") (pin "24") (pinfunction "24_24") (pintype "bidirectional"))
    )
    (net (code "30") (name "Net-(IC1-TS{slash}MR)") (class "Default")
      (node (ref "IC1") (pin "D1") (pinfunction "TS/MR_D1") (pintype "bidirectional"))
      (node (ref "R9") (pin "2") (pinfunction "2_2") (pintype "bidirectional"))
    )
    (net (code "31") (name "Net-(IC2-REG)") (class "Default")
      (node (ref "C32") (pin "2") (pinfunction "2_2") (pintype "passive"))
      (node (ref "IC2") (pin "A2") (pinfunction "REG_A2") (pintype "bidirectional"))
    )
    (net (code "32") (name "Net-(IC3-SDO)") (class "Default")
      (node (ref "IC3") (pin "1") (pinfunction "SDO_1") (pintype "bidirectional"))
      (node (ref "R3") (pin "2") (pinfunction "2_2") (pintype "bidirectional"))
    )
    (net (code "33") (name "Net-(IC9-SCL)") (class "Default")
      (node (ref "IC9") (pin "D1") (pinfunction "SCL_D1") (pintype "bidirectional"))
      (node (ref "R4") (pin "2") (pinfunction "2_2") (pintype "bidirectional"))
    )
    (net (code "34") (name "Net-(IC9-SDA)") (class "Default")
      (node (ref "IC9") (pin "E1") (pinfunction "SDA_E1") (pintype "bidirectional"))
      (node (ref "R2") (pin "2") (pinfunction "2_2") (pintype "bidirectional"))
    )
    (net (code "35") (name "Net-(J4-CC1)") (class "Default")
      (node (ref "J4") (pin "A5") (pinfunction "CC1_A5") (pintype "bidirectional"))
      (node (ref "R1_USB") (pin "2") (pinfunction "2_2") (pintype "bidirectional"))
    )
    (net (code "36") (name "Net-(J4-CC2)") (class "Default")
      (node (ref "J4") (pin "B5") (pinfunction "CC2_B5") (pintype "bidirectional"))
      (node (ref "R2_USB") (pin "1") (pinfunction "1_1") (pintype "bidirectional"))
    )
    (net (code "37") (name "Net-(L2-Pad2)") (class "Default")
      (node (ref "L2") (pin "2") (pinfunction "2_2") (pintype "passive"))
      (node (ref "L3") (pin "1") (pinfunction "1_1") (pintype "passive"))
    )
    (net (code "38") (name "Net-(R1_EP_DR-Pad1)") (class "Default")
      (node (ref "R1_EP_DR") (pin "1") (pinfunction "1_1") (pintype "bidirectional"))
      (node (ref "R_TYPE_SEL") (pin "2") (pinfunction "2_2") (pintype "bidirectional"))
      (node (ref "SJ1") (pin "2") (pinfunction "2_2") (pintype "passive"))
    )
    (net (code "39") (name "Net-(U1-ANT)") (class "Default")
      (node (ref "C3") (pin "1") (pinfunction "1_1") (pintype "passive"))
      (node (ref "L1") (pin "1") (pinfunction "1_1") (pintype "passive"))
      (node (ref "U1") (pin "P$H23") (pinfunction "ANT_P$H23") (pintype "bidirectional"))
    )
    (net (code "40") (name "Net-(U1-DCC)") (class "Default")
      (node (ref "L2") (pin "1") (pinfunction "1_1") (pintype "passive"))
      (node (ref "U1") (pin "P$B3") (pinfunction "DCC_P$B3") (pintype "output"))
    )
    (net (code "41") (name "Net-(U1-DEC1)") (class "Default")
      (node (ref "C5") (pin "1") (pinfunction "1_1") (pintype "passive"))
      (node (ref "U1") (pin "P$C1") (pinfunction "DEC1_P$C1") (pintype "power_in"))
    )
    (net (code "42") (name "Net-(U1-DEC2)") (class "Default")
      (node (ref "C13") (pin "1") (pinfunction "1_1") (pintype "passive"))
      (node (ref "U1") (pin "P$A18") (pinfunction "DEC2_P$A18") (pintype "bidirectional"))
    )
    (net (code "43") (name "Net-(U1-DEC3)") (class "Default")
      (node (ref "C11") (pin "1") (pinfunction "1_1") (pintype "passive"))
      (node (ref "U1") (pin "P$D23") (pinfunction "DEC3_P$D23") (pintype "bidirectional"))
    )
    (net (code "44") (name "Net-(U1-DEC3V3)") (class "Default")
      (node (ref "C20") (pin "1") (pinfunction "1_1") (pintype "passive"))
      (node (ref "U1") (pin "P$AC5") (pinfunction "DEC3V3_P$AC5") (pintype "bidirectional"))
    )
    (net (code "45") (name "Net-(U1-DEC4)") (class "Default")
      (node (ref "C10") (pin "1") (pinfunction "1_1") (pintype "passive"))
      (node (ref "C15") (pin "1") (pinfunction "1_1") (pintype "passive"))
      (node (ref "C16") (pin "1") (pinfunction "1_1") (pintype "passive"))
      (node (ref "L3") (pin "2") (pinfunction "2_2") (pintype "passive"))
      (node (ref "U1") (pin "P$B5") (pinfunction "DEC4_P$B5") (pintype "power_in"))
      (node (ref "U1") (pin "P$E24") (pinfunction "DEC6_P$E24") (pintype "bidirectional"))
    )
    (net (code "46") (name "Net-(U1-DEC5)") (class "Default")
      (node (ref "C9") (pin "1") (pinfunction "1_1") (pintype "passive"))
      (node (ref "U1") (pin "P$N24") (pinfunction "DEC5_P$N24") (pintype "bidirectional"))
    )
    (net (code "47") (name "Net-(U1-P0.00{slash}XL1)") (class "Default")
      (node (ref "C17") (pin "1") (pinfunction "1_1") (pintype "passive"))
      (node (ref "U1") (pin "P$D2") (pinfunction "P0.00/XL1_P$D2") (pintype "bidirectional"))
      (node (ref "X2") (pin "1") (pinfunction "1_1") (pintype "passive"))
    )
    (net (code "48") (name "Net-(U1-P0.01{slash}XL2)") (class "Default")
      (node (ref "C18") (pin "2") (pinfunction "2_2") (pintype "passive"))
      (node (ref "U1") (pin "P$F2") (pinfunction "P0.01/XL2_P$F2") (pintype "bidirectional"))
      (node (ref "X2") (pin "2") (pinfunction "2_2") (pintype "passive"))
    )
    (net (code "49") (name "Net-(U1-XC1)") (class "Default")
      (node (ref "C1") (pin "2") (pinfunction "2_2") (pintype "passive"))
      (node (ref "U1") (pin "P$B24") (pinfunction "XC1_P$B24") (pintype "input"))
      (node (ref "X1") (pin "1") (pinfunction "1_1") (pintype "passive"))
    )
    (net (code "50") (name "Net-(U1-XC2)") (class "Default")
      (node (ref "C2") (pin "1") (pinfunction "1_1") (pintype "passive"))
      (node (ref "U1") (pin "P$A23") (pinfunction "XC2_P$A23") (pintype "output"))
      (node (ref "X1") (pin "3") (pinfunction "3_3") (pintype "passive"))
    )
    (net (code "51") (name "OUT+") (class "Default")
      (node (ref "IC2") (pin "A3") (pinfunction "OUT+_A3") (pintype "bidirectional"))
      (node (ref "TP_OP") (pin "TP") (pinfunction "TP_TP") (pintype "input"))
    )
    (net (code "52") (name "OUT-") (class "Default")
      (node (ref "IC2") (pin "C3") (pinfunction "OUT-_C3") (pintype "bidirectional"))
      (node (ref "TP_ON") (pin "TP") (pinfunction "TP_TP") (pintype "input"))
    )
    (net (code "53") (name "P0.04") (class "Default")
      (node (ref "U1") (pin "P$J1") (pinfunction "P0.04/AIN2_P$J1") (pintype "bidirectional"))
    )
    (net (code "54") (name "P0.09") (class "Default")
      (node (ref "U1") (pin "P$L24") (pinfunction "P0.09/NFC1_P$L24") (pintype "bidirectional"))
    )
    (net (code "55") (name "P0.13") (class "Default")
      (node (ref "C30") (pin "2") (pinfunction "2_2") (pintype "passive"))
      (node (ref "R5") (pin "1") (pinfunction "1_1") (pintype "bidirectional"))
      (node (ref "SW_UP") (pin "2") (pinfunction "2_2") (pintype "passive"))
      (node (ref "U1") (pin "P$AD8") (pinfunction "P0.13_P$AD8") (pintype "bidirectional"))
    )
    (net (code "56") (name "P0.14") (class "Default")
      (node (ref "C31") (pin "2") (pinfunction "2_2") (pintype "passive"))
      (node (ref "R8") (pin "1") (pinfunction "1_1") (pintype "bidirectional"))
      (node (ref "SW_ENT") (pin "2") (pinfunction "2_2") (pintype "passive"))
      (node (ref "U1") (pin "P$AC9") (pinfunction "P0.14_P$AC9") (pintype "bidirectional"))
    )
    (net (code "57") (name "P0.19") (class "Default")
      (node (ref "U1") (pin "P$AC15") (pinfunction "P0.19_P$AC15") (pintype "bidirectional"))
    )
    (net (code "58") (name "P0.20") (class "Default")
      (node (ref "U1") (pin "P$AD16") (pinfunction "P0.20_P$AD16") (pintype "bidirectional"))
    )
    (net (code "59") (name "P0.21") (class "Default")
      (node (ref "U1") (pin "P$AC17") (pinfunction "P0.21_P$AC17") (pintype "bidirectional"))
    )
    (net (code "60") (name "P0.22") (class "Default")
      (node (ref "U1") (pin "P$AD18") (pinfunction "P0.22_P$AD18") (pintype "bidirectional"))
    )
    (net (code "61") (name "P0.23") (class "Default")
      (node (ref "U1") (pin "P$AC19") (pinfunction "P0.23_P$AC19") (pintype "bidirectional"))
    )
    (net (code "62") (name "P0.24") (class "Default")
      (node (ref "U1") (pin "P$AD20") (pinfunction "P0.24_P$AD20") (pintype "bidirectional"))
    )
    (net (code "63") (name "P0.25") (class "Default")
      (node (ref "U1") (pin "P$AC21") (pinfunction "P0.25_P$AC21") (pintype "bidirectional"))
    )
    (net (code "64") (name "P0.26") (class "Default")
      (node (ref "U1") (pin "P$G1") (pinfunction "P0.26_P$G1") (pintype "bidirectional"))
    )
    (net (code "65") (name "P0.27") (class "Default")
      (node (ref "U1") (pin "P$H2") (pinfunction "P0.27_P$H2") (pintype "bidirectional"))
    )
    (net (code "66") (name "P0.28") (class "Default")
      (node (ref "U1") (pin "P$B11") (pinfunction "P0.28/AIN4_P$B11") (pintype "bidirectional"))
    )
    (net (code "67") (name "P0.29") (class "Default")
      (node (ref "U1") (pin "P$A10") (pinfunction "P0.29/AIN5_P$A10") (pintype "bidirectional"))
    )
    (net (code "68") (name "P0.30") (class "Default")
      (node (ref "U1") (pin "P$B9") (pinfunction "P0.30/AIN6_P$B9") (pintype "bidirectional"))
    )
    (net (code "69") (name "P0.31") (class "Default")
      (node (ref "U1") (pin "P$A8") (pinfunction "P0.31/AIN7_P$A8") (pintype "bidirectional"))
    )
    (net (code "70") (name "P1.01") (class "Default")
      (node (ref "Q1") (pin "1") (pinfunction "G_1") (pintype "bidirectional"))
      (node (ref "R_PWR_EPD") (pin "1") (pinfunction "1_1") (pintype "bidirectional"))
      (node (ref "U1") (pin "P$Y23") (pinfunction "P1.01_P$Y23") (pintype "bidirectional"))
    )
    (net (code "71") (name "P1.02") (class "Default")
      (node (ref "C29") (pin "2") (pinfunction "2_2") (pintype "passive"))
      (node (ref "R7") (pin "1") (pinfunction "1_1") (pintype "bidirectional"))
      (node (ref "SW_DN") (pin "2") (pinfunction "2_2") (pintype "passive"))
      (node (ref "U1") (pin "P$W24") (pinfunction "P1.02_P$W24") (pintype "bidirectional"))
    )
    (net (code "72") (name "P1.03") (class "Default")
      (node (ref "U1") (pin "P$V23") (pinfunction "P1.03_P$V23") (pintype "bidirectional"))
    )
    (net (code "73") (name "P1.04") (class "Default")
      (node (ref "U1") (pin "P$U24") (pinfunction "P1.04_P$U24") (pintype "bidirectional"))
    )
    (net (code "74") (name "P1.05") (class "Default")
      (node (ref "U1") (pin "P$T23") (pinfunction "P1.05_P$T23") (pintype "bidirectional"))
    )
    (net (code "75") (name "P1.06") (class "Default")
      (node (ref "U1") (pin "P$R24") (pinfunction "P1.06_P$R24") (pintype "bidirectional"))
    )
    (net (code "76") (name "P1.07") (class "Default")
      (node (ref "U1") (pin "P$P23") (pinfunction "P1.07_P$P23") (pintype "bidirectional"))
    )
    (net (code "77") (name "P1.09") (class "Default")
      (node (ref "U1") (pin "P$R1") (pinfunction "P1.09_P$R1") (pintype "bidirectional"))
    )
    (net (code "78") (name "P1.10") (class "Default")
      (node (ref "U1") (pin "P$A20") (pinfunction "P1.10_P$A20") (pintype "bidirectional"))
    )
    (net (code "79") (name "P1.11") (class "Default")
      (node (ref "U1") (pin "P$B19") (pinfunction "P1.11_P$B19") (pintype "bidirectional"))
    )
    (net (code "80") (name "P1.12") (class "Default")
      (node (ref "U1") (pin "P$B17") (pinfunction "P1.12_P$B17") (pintype "bidirectional"))
    )
    (net (code "81") (name "P1.13") (class "Default")
      (node (ref "U1") (pin "P$A16") (pinfunction "P1.13_P$A16") (pintype "bidirectional"))
    )
    (net (code "82") (name "P1.14") (class "Default")
      (node (ref "U1") (pin "P$B15") (pinfunction "P1.14_P$B15") (pintype "bidirectional"))
    )
    (net (code "83") (name "P1.15") (class "Default")
      (node (ref "U1") (pin "P$A14") (pinfunction "P1.15_P$A14") (pintype "bidirectional"))
    )
    (net (code "84") (name "PMIC_INT") (class "Default")
      (node (ref "IC1") (pin "A1") (pinfunction "~{INT}_A1") (pintype "bidirectional"))
      (node (ref "U1") (pin "P$T2") (pinfunction "P0.11_P$T2") (pintype "bidirectional"))
    )
    (net (code "85") (name "PREVGH") (class "Default")
      (node (ref "D5") (pin "1") (pinfunction "K_1") (pintype "bidirectional"))
      (node (ref "EPD_C9") (pin "2") (pinfunction "2_2") (pintype "passive"))
      (node (ref "J1") (pin "21") (pinfunction "21_21") (pintype "bidirectional"))
    )
    (net (code "86") (name "PREVGL") (class "Default")
      (node (ref "D2") (pin "2") (pinfunction "A_2") (pintype "bidirectional"))
      (node (ref "EPD_C11") (pin "2") (pinfunction "2_2") (pintype "passive"))
      (node (ref "J1") (pin "23") (pinfunction "23_23") (pintype "bidirectional"))
    )
    (net (code "87") (name "RESE") (class "Default")
      (node (ref "J1") (pin "3") (pinfunction "3_3") (pintype "bidirectional"))
      (node (ref "Q3") (pin "2") (pinfunction "S_2") (pintype "bidirectional"))
      (node (ref "R1_EP_DR") (pin "2") (pinfunction "2_2") (pintype "bidirectional"))
    )
    (net (code "88") (name "RESET") (class "Default")
      (node (ref "J2") (pin "6") (pinfunction "6_6") (pintype "bidirectional"))
      (node (ref "TP_RESET") (pin "TP") (pinfunction "TP_TP") (pintype "input"))
      (node (ref "U1") (pin "P$AC13") (pinfunction "P0.18/RESET_P$AC13") (pintype "bidirectional"))
    )
    (net (code "89") (name "SCK") (class "Default")
      (node (ref "J1") (pin "13") (pinfunction "13_13") (pintype "bidirectional"))
      (node (ref "U1") (pin "P$A12") (pinfunction "P0.02/AIN0_P$A12") (pintype "bidirectional"))
    )
    (net (code "90") (name "SCL") (class "Default")
      (node (ref "IC1") (pin "B1") (pinfunction "SCL_B1") (pintype "bidirectional"))
      (node (ref "IC2") (pin "C1") (pinfunction "SCL_C1") (pintype "bidirectional"))
      (node (ref "IC3") (pin "12") (pinfunction "SCX_12") (pintype "bidirectional"))
      (node (ref "R17") (pin "2") (pinfunction "2_2") (pintype "bidirectional"))
      (node (ref "R2") (pin "1") (pinfunction "1_1") (pintype "bidirectional"))
      (node (ref "R4") (pin "1") (pinfunction "1_1") (pintype "bidirectional"))
      (node (ref "TP_SCL") (pin "TP") (pinfunction "TP_TP") (pintype "input"))
      (node (ref "U1") (pin "P$M2") (pinfunction "P0.07_P$M2") (pintype "bidirectional"))
      (node (ref "U3") (pin "7") (pinfunction "SCL_7") (pintype "input"))
    )
    (net (code "91") (name "SDA") (class "Default")
      (node (ref "IC1") (pin "C1") (pinfunction "SDA_C1") (pintype "bidirectional"))
      (node (ref "IC2") (pin "B2") (pinfunction "SDA_B2") (pintype "bidirectional"))
      (node (ref "IC3") (pin "2") (pinfunction "SDX_2") (pintype "bidirectional"))
      (node (ref "R18") (pin "2") (pinfunction "2_2") (pintype "bidirectional"))
      (node (ref "TP_SDA") (pin "TP") (pinfunction "TP_TP") (pintype "input"))
      (node (ref "U1") (pin "P$L1") (pinfunction "P0.06_P$L1") (pintype "bidirectional"))
      (node (ref "U3") (pin "8") (pinfunction "SDA_8") (pintype "bidirectional"))
    )
    (net (code "92") (name "SWDCLK") (class "Default")
      (node (ref "J2") (pin "4") (pinfunction "4_4") (pintype "bidirectional"))
      (node (ref "TP_SWDCLK") (pin "TP") (pinfunction "TP_TP") (pintype "input"))
      (node (ref "U1") (pin "P$AA24") (pinfunction "SWDCLK_P$AA24") (pintype "input"))
    )
    (net (code "93") (name "SWDIO") (class "Default")
      (node (ref "J2") (pin "2") (pinfunction "2_2") (pintype "bidirectional"))
      (node (ref "TP_SWDIO") (pin "TP") (pinfunction "TP_TP") (pintype "input"))
      (node (ref "U1") (pin "P$AC24") (pinfunction "SWDIO_P$AC24") (pintype "bidirectional"))
    )
    (net (code "94") (name "SWO") (class "Default")
      (node (ref "TP_SWO") (pin "TP") (pinfunction "TP_TP") (pintype "input"))
      (node (ref "U1") (pin "P$AD22") (pinfunction "P1.00_P$AD22") (pintype "bidirectional"))
    )
    (net (code "95") (name "VBAT") (class "Default")
      (node (ref "C27") (pin "2") (pinfunction "2_2") (pintype "passive"))
      (node (ref "C37") (pin "2") (pinfunction "2_2") (pintype "passive"))
      (node (ref "IC1") (pin "C2") (pinfunction "BAT_C2") (pintype "bidirectional"))
      (node (ref "TP_VBAT") (pin "TP") (pinfunction "TP_TP") (pintype "input"))
      (node (ref "U3") (pin "2") (pinfunction "CELL_2") (pintype "power_in"))
      (node (ref "U3") (pin "3") (pinfunction "VDD_3") (pintype "power_in"))
    )
    (net (code "96") (name "VBUS") (class "Default")
      (node (ref "C21") (pin "1") (pinfunction "1_1") (pintype "passive"))
      (node (ref "C38") (pin "2") (pinfunction "2_2") (pintype "passive"))
      (node (ref "C42") (pin "2") (pinfunction "2_2") (pintype "passive"))
      (node (ref "C43") (pin "1") (pinfunction "1_1") (pintype "passive"))
      (node (ref "D3") (pin "5") (pinfunction "VBUS_5") (pintype "bidirectional"))
      (node (ref "IC1") (pin "A2") (pinfunction "IN_A2") (pintype "bidirectional"))
      (node (ref "J4") (pin "A4_B9") (pinfunction "VBUS_A4_B9") (pintype "power_in"))
      (node (ref "J4") (pin "A9_B4") (pinfunction "VBUS_A9_B4") (pintype "power_in"))
      (node (ref "U1") (pin "P$AD2") (pinfunction "VBUS_P$AD2") (pintype "power_in"))
    )
    (net (code "97") (name "VREG") (class "Default")
      (node (ref "C23") (pin "1") (pinfunction "1_1") (pintype "passive"))
      (node (ref "C24") (pin "2") (pinfunction "2_2") (pintype "passive"))
      (node (ref "C39") (pin "1") (pinfunction "1_1") (pintype "passive"))
      (node (ref "IC1") (pin "B2") (pinfunction "SYS_B2") (pintype "bidirectional"))
      (node (ref "IC9") (pin "A1") (pinfunction "EN_A1") (pintype "bidirectional"))
      (node (ref "IC9") (pin "A2") (pinfunction "VIN_1_A2") (pintype "bidirectional"))
      (node (ref "IC9") (pin "A3") (pinfunction "VIN_2_A3") (pintype "bidirectional"))
      (node (ref "TP_VREG") (pin "TP") (pinfunction "TP_TP") (pintype "input"))
    )
    (net (code "98") (name "unconnected-(ANT1-NC-Pad2)") (class "Default")
      (node (ref "ANT1") (pin "2") (pinfunction "NC_2") (pintype "no_connect"))
    )
    (net (code "99") (name "unconnected-(IC3-ASCL-Pad11)") (class "Default")
      (node (ref "IC3") (pin "11") (pinfunction "ASCL_11") (pintype "bidirectional"))
    )
    (net (code "100") (name "unconnected-(IC3-ASDA-Pad4)") (class "Default")
      (node (ref "IC3") (pin "4") (pinfunction "ASDA_4") (pintype "bidirectional"))
    )
    (net (code "101") (name "unconnected-(J1-Pad1)") (class "Default")
      (node (ref "J1") (pin "1") (pinfunction "1_1") (pintype "bidirectional"))
    )
    (net (code "102") (name "unconnected-(J1-Pad6)") (class "Default")
      (node (ref "J1") (pin "6") (pinfunction "6_6") (pintype "bidirectional"))
    )
    (net (code "103") (name "unconnected-(J1-Pad7)") (class "Default")
      (node (ref "J1") (pin "7") (pinfunction "7_7") (pintype "bidirectional"))
    )
    (net (code "104") (name "unconnected-(J4-SBU1-PadA8)") (class "Default")
      (node (ref "J4") (pin "A8") (pinfunction "SBU1_A8") (pintype "bidirectional"))
    )
    (net (code "105") (name "unconnected-(J4-SBU2-PadB8)") (class "Default")
      (node (ref "J4") (pin "B8") (pinfunction "SBU2_B8") (pintype "bidirectional"))
    )
    (net (code "106") (name "unconnected-(R7-Pad2)") (class "Default")
      (node (ref "R7") (pin "2") (pinfunction "2_2") (pintype "bidirectional"))
    )
    (net (code "107") (name "unconnected-(R8-Pad2)") (class "Default")
      (node (ref "R8") (pin "2") (pinfunction "2_2") (pintype "bidirectional"))
    )
    (net (code "108") (name "unconnected-(U1-DCCH-PadP$AB2)") (class "Default")
      (node (ref "U1") (pin "P$AB2") (pinfunction "DCCH_P$AB2") (pintype "bidirectional"))
    )
  )
)
